# 04_LemonAutopilot_4.net
KiCad netlist of a schematic drawn in Altium Designer
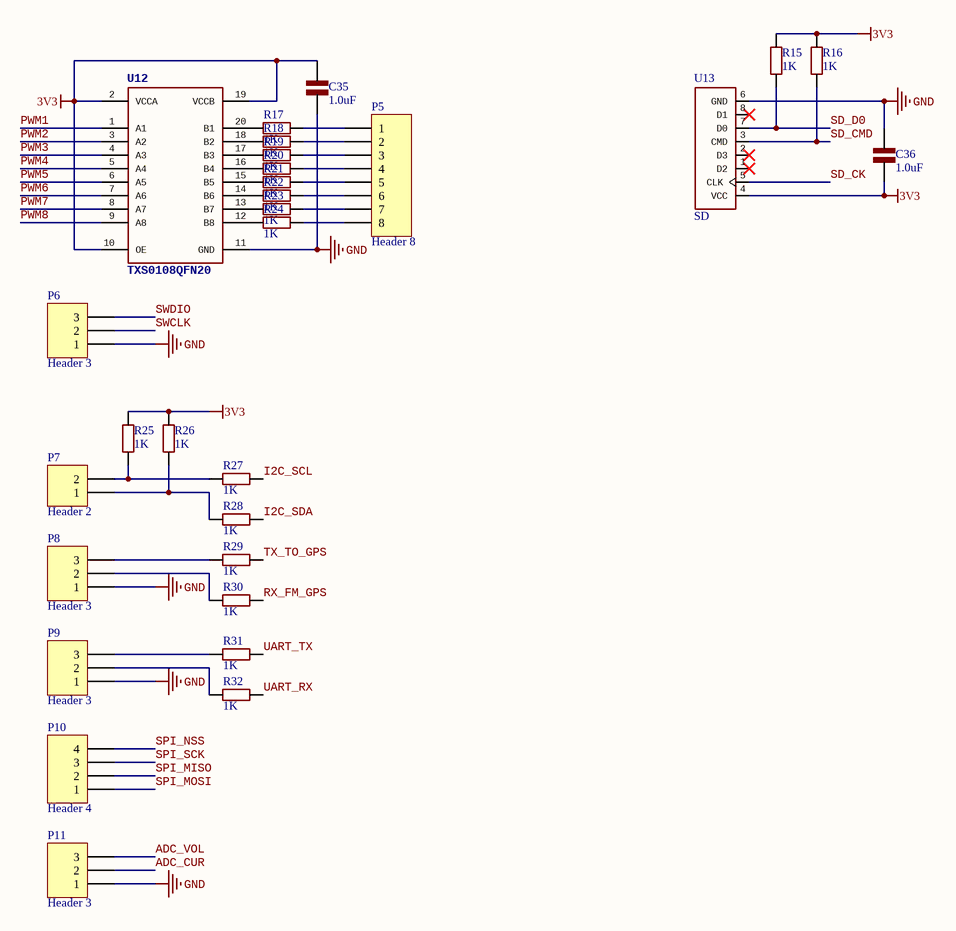
[diagram p0: 04.LemonAutopilot_4.SchDoc]

(export (version "E")
  (design (tool "Eeschema 10.0.6"))
  (components
    (comp (ref "C35") (value "1.0uF") (footprint "0603_C") (libsource (lib "Library") (part "C0603")))
    (comp (ref "C36") (value "1.0uF") (footprint "0603_C") (libsource (lib "Library") (part "C0603")))
    (comp (ref "P5")
      (value "Header 8")
      (footprint "HDR1X8")
      (description "Header, 8-Pin")
      (fields (field (name "PUBLISHER") "Altium Limited"))
      (libsource (lib "Miscellaneous Connectors") (part "Header 8"))
    )
    (comp (ref "P6")
      (value "Header 3")
      (footprint "HDR1X3")
      (description "Header, 3-Pin")
      (fields (field (name "PUBLISHER") "Altium Limited"))
      (libsource (lib "Miscellaneous Connectors") (part "Header 3"))
    )
    (comp (ref "P7")
      (value "Header 2")
      (footprint "HDR1X2")
      (description "Header, 2-Pin")
      (fields (field (name "PUBLISHER") "Altium Limited"))
      (libsource (lib "Miscellaneous Connectors") (part "Header 2"))
    )
    (comp (ref "P8")
      (value "Header 3")
      (footprint "HDR1X3")
      (description "Header, 3-Pin")
      (fields (field (name "PUBLISHER") "Altium Limited"))
      (libsource (lib "Miscellaneous Connectors") (part "Header 3"))
    )
    (comp (ref "P9")
      (value "Header 3")
      (footprint "HDR1X3")
      (description "Header, 3-Pin")
      (fields (field (name "PUBLISHER") "Altium Limited"))
      (libsource (lib "Miscellaneous Connectors") (part "Header 3"))
    )
    (comp (ref "P10")
      (value "Header 4")
      (footprint "HDR1X4")
      (description "Header, 4-Pin")
      (fields (field (name "PUBLISHER") "Altium Limited"))
      (libsource (lib "Miscellaneous Connectors") (part "Header 4"))
    )
    (comp (ref "P11")
      (value "Header 3")
      (footprint "HDR1X3")
      (description "Header, 3-Pin")
      (fields (field (name "PUBLISHER") "Altium Limited"))
      (libsource (lib "Miscellaneous Connectors") (part "Header 3"))
    )
    (comp (ref "R15") (value "1K") (footprint "0603_R") (libsource (lib "") (part "R0603_1")))
    (comp (ref "R16") (value "1K") (footprint "0603_R") (libsource (lib "") (part "R0603_1")))
    (comp (ref "R17") (value "1K") (footprint "0603_R") (libsource (lib "Library") (part "R0603")))
    (comp (ref "R18") (value "1K") (footprint "0603_R") (libsource (lib "Library") (part "R0603")))
    (comp (ref "R19") (value "1K") (footprint "0603_R") (libsource (lib "Library") (part "R0603")))
    (comp (ref "R20") (value "1K") (footprint "0603_R") (libsource (lib "Library") (part "R0603")))
    (comp (ref "R21") (value "1K") (footprint "0603_R") (libsource (lib "Library") (part "R0603")))
    (comp (ref "R22") (value "1K") (footprint "0603_R") (libsource (lib "Library") (part "R0603")))
    (comp (ref "R23") (value "1K") (footprint "0603_R") (libsource (lib "Library") (part "R0603")))
    (comp (ref "R24") (value "1K") (footprint "0603_R") (libsource (lib "Library") (part "R0603")))
    (comp (ref "R25") (value "1K") (footprint "0603_R") (libsource (lib "") (part "R0603_1")))
    (comp (ref "R26") (value "1K") (footprint "0603_R") (libsource (lib "") (part "R0603_1")))
    (comp (ref "R27") (value "1K") (footprint "0603_R") (libsource (lib "Library") (part "R0603")))
    (comp (ref "R28") (value "1K") (footprint "0603_R") (libsource (lib "Library") (part "R0603")))
    (comp (ref "R29") (value "1K") (footprint "0603_R") (libsource (lib "Library") (part "R0603")))
    (comp (ref "R30") (value "1K") (footprint "0603_R") (libsource (lib "Library") (part "R0603")))
    (comp (ref "R31") (value "1K") (footprint "0603_R") (libsource (lib "Library") (part "R0603")))
    (comp (ref "R32") (value "1K") (footprint "0603_R") (libsource (lib "Library") (part "R0603")))
    (comp (ref "U12")
      (value "TXS0108QFN20")
      (footprint "QFN20-RGY")
      (libsource (lib "Library") (part "TXS0108QFN20"))
    )
    (comp (ref "U13") (value "SD") (libsource (lib "Library") (part "SD")))
  )
  (nets
    (net (code "1") (name "/ADC_CUR") (class "Default")
      (node (ref "P11") (pin "2") (pinfunction "2_2") (pintype "passive"))
    )
    (net (code "2") (name "/ADC_VOL") (class "Default")
      (node (ref "P11") (pin "3") (pinfunction "3_3") (pintype "passive"))
    )
    (net (code "3") (name "/I2C_SCL") (class "Default")
      (node (ref "R27") (pin "2") (pinfunction "2_2") (pintype "passive"))
    )
    (net (code "4") (name "/I2C_SDA") (class "Default")
      (node (ref "R28") (pin "2") (pinfunction "2_2") (pintype "passive"))
    )
    (net (code "5") (name "/PWM1") (class "Default")
      (node (ref "U12") (pin "1") (pinfunction "A1_1") (pintype "passive"))
    )
    (net (code "6") (name "/PWM2") (class "Default")
      (node (ref "U12") (pin "3") (pinfunction "A2_3") (pintype "passive"))
    )
    (net (code "7") (name "/PWM3") (class "Default")
      (node (ref "U12") (pin "4") (pinfunction "A3_4") (pintype "passive"))
    )
    (net (code "8") (name "/PWM4") (class "Default")
      (node (ref "U12") (pin "5") (pinfunction "A4_5") (pintype "passive"))
    )
    (net (code "9") (name "/PWM5") (class "Default")
      (node (ref "U12") (pin "6") (pinfunction "A5_6") (pintype "passive"))
    )
    (net (code "10") (name "/PWM6") (class "Default")
      (node (ref "U12") (pin "7") (pinfunction "A6_7") (pintype "passive"))
    )
    (net (code "11") (name "/PWM7") (class "Default")
      (node (ref "U12") (pin "8") (pinfunction "A7_8") (pintype "passive"))
    )
    (net (code "12") (name "/PWM8") (class "Default")
      (node (ref "U12") (pin "9") (pinfunction "A8_9") (pintype "passive"))
    )
    (net (code "13") (name "/RX_FM_GPS") (class "Default")
      (node (ref "R30") (pin "2") (pinfunction "2_2") (pintype "passive"))
    )
    (net (code "14") (name "/SD_CK") (class "Default")
      (node (ref "U13") (pin "5") (pinfunction "CLK_5") (pintype "passive"))
    )
    (net (code "15") (name "/SD_CMD") (class "Default")
      (node (ref "R16") (pin "2") (pinfunction "2_2") (pintype "passive"))
      (node (ref "U13") (pin "3") (pinfunction "CMD_3") (pintype "passive"))
    )
    (net (code "16") (name "/SD_D0") (class "Default")
      (node (ref "R15") (pin "2") (pinfunction "2_2") (pintype "passive"))
      (node (ref "U13") (pin "7") (pinfunction "D0_7") (pintype "passive"))
    )
    (net (code "17") (name "/SPI_MISO") (class "Default")
      (node (ref "P10") (pin "2") (pinfunction "2_2") (pintype "passive"))
    )
    (net (code "18") (name "/SPI_MOSI") (class "Default")
      (node (ref "P10") (pin "1") (pinfunction "1_1") (pintype "passive"))
    )
    (net (code "19") (name "/SPI_NSS") (class "Default")
      (node (ref "P10") (pin "4") (pinfunction "4_4") (pintype "passive"))
    )
    (net (code "20") (name "/SPI_SCK") (class "Default")
      (node (ref "P10") (pin "3") (pinfunction "3_3") (pintype "passive"))
    )
    (net (code "21") (name "/SWCLK") (class "Default")
      (node (ref "P6") (pin "2") (pinfunction "2_2") (pintype "passive"))
    )
    (net (code "22") (name "/SWDIO") (class "Default")
      (node (ref "P6") (pin "3") (pinfunction "3_3") (pintype "passive"))
    )
    (net (code "23") (name "/TX_TO_GPS") (class "Default")
      (node (ref "R29") (pin "2") (pinfunction "2_2") (pintype "passive"))
    )
    (net (code "24") (name "/UART_RX") (class "Default")
      (node (ref "R32") (pin "2") (pinfunction "2_2") (pintype "passive"))
    )
    (net (code "25") (name "/UART_TX") (class "Default")
      (node (ref "R31") (pin "2") (pinfunction "2_2") (pintype "passive"))
    )
    (net (code "26") (name "3V3") (class "Default")
      (node (ref "C35") (pin "2") (pinfunction "2_2") (pintype "passive"))
      (node (ref "C36") (pin "1") (pinfunction "1_1") (pintype "passive"))
      (node (ref "R15") (pin "1") (pinfunction "1_1") (pintype "passive"))
      (node (ref "R16") (pin "1") (pinfunction "1_1") (pintype "passive"))
      (node (ref "R25") (pin "1") (pinfunction "1_1") (pintype "passive"))
      (node (ref "R26") (pin "1") (pinfunction "1_1") (pintype "passive"))
      (node (ref "U12") (pin "10") (pinfunction "OE_10") (pintype "passive"))
      (node (ref "U12") (pin "19") (pinfunction "VCCB_19") (pintype "passive"))
      (node (ref "U12") (pin "2") (pinfunction "VCCA_2") (pintype "passive"))
      (node (ref "U13") (pin "4") (pinfunction "VCC_4") (pintype "passive"))
    )
    (net (code "27") (name "GND") (class "Default")
      (node (ref "C35") (pin "1") (pinfunction "1_1") (pintype "passive"))
      (node (ref "C36") (pin "2") (pinfunction "2_2") (pintype "passive"))
      (node (ref "P11") (pin "1") (pinfunction "1_1") (pintype "passive"))
      (node (ref "P6") (pin "1") (pinfunction "1_1") (pintype "passive"))
      (node (ref "P8") (pin "1") (pinfunction "1_1") (pintype "passive"))
      (node (ref "P9") (pin "1") (pinfunction "1_1") (pintype "passive"))
      (node (ref "U12") (pin "11") (pinfunction "GND_11") (pintype "power_in"))
      (node (ref "U13") (pin "6") (pinfunction "GND_6") (pintype "power_in"))
    )
    (net (code "28") (name "Net-(P5-Pad1)") (class "Default")
      (node (ref "P5") (pin "1") (pinfunction "1_1") (pintype "passive"))
      (node (ref "R17") (pin "2") (pinfunction "2_2") (pintype "passive"))
    )
    (net (code "29") (name "Net-(P5-Pad2)") (class "Default")
      (node (ref "P5") (pin "2") (pinfunction "2_2") (pintype "passive"))
      (node (ref "R18") (pin "2") (pinfunction "2_2") (pintype "passive"))
    )
    (net (code "30") (name "Net-(P5-Pad3)") (class "Default")
      (node (ref "P5") (pin "3") (pinfunction "3_3") (pintype "passive"))
      (node (ref "R19") (pin "2") (pinfunction "2_2") (pintype "passive"))
    )
    (net (code "31") (name "Net-(P5-Pad4)") (class "Default")
      (node (ref "P5") (pin "4") (pinfunction "4_4") (pintype "passive"))
      (node (ref "R20") (pin "2") (pinfunction "2_2") (pintype "passive"))
    )
    (net (code "32") (name "Net-(P5-Pad5)") (class "Default")
      (node (ref "P5") (pin "5") (pinfunction "5_5") (pintype "passive"))
      (node (ref "R21") (pin "2") (pinfunction "2_2") (pintype "passive"))
    )
    (net (code "33") (name "Net-(P5-Pad6)") (class "Default")
      (node (ref "P5") (pin "6") (pinfunction "6_6") (pintype "passive"))
      (node (ref "R22") (pin "2") (pinfunction "2_2") (pintype "passive"))
    )
    (net (code "34") (name "Net-(P5-Pad7)") (class "Default")
      (node (ref "P5") (pin "7") (pinfunction "7_7") (pintype "passive"))
      (node (ref "R23") (pin "2") (pinfunction "2_2") (pintype "passive"))
    )
    (net (code "35") (name "Net-(P5-Pad8)") (class "Default")
      (node (ref "P5") (pin "8") (pinfunction "8_8") (pintype "passive"))
      (node (ref "R24") (pin "2") (pinfunction "2_2") (pintype "passive"))
    )
    (net (code "36") (name "Net-(P7-Pad1)") (class "Default")
      (node (ref "P7") (pin "1") (pinfunction "1_1") (pintype "passive"))
      (node (ref "R26") (pin "2") (pinfunction "2_2") (pintype "passive"))
      (node (ref "R28") (pin "1") (pinfunction "1_1") (pintype "passive"))
    )
    (net (code "37") (name "Net-(P7-Pad2)") (class "Default")
      (node (ref "P7") (pin "2") (pinfunction "2_2") (pintype "passive"))
      (node (ref "R25") (pin "2") (pinfunction "2_2") (pintype "passive"))
      (node (ref "R27") (pin "1") (pinfunction "1_1") (pintype "passive"))
    )
    (net (code "38") (name "Net-(P8-Pad2)") (class "Default")
      (node (ref "P8") (pin "2") (pinfunction "2_2") (pintype "passive"))
      (node (ref "R30") (pin "1") (pinfunction "1_1") (pintype "passive"))
    )
    (net (code "39") (name "Net-(P8-Pad3)") (class "Default")
      (node (ref "P8") (pin "3") (pinfunction "3_3") (pintype "passive"))
      (node (ref "R29") (pin "1") (pinfunction "1_1") (pintype "passive"))
    )
    (net (code "40") (name "Net-(P9-Pad2)") (class "Default")
      (node (ref "P9") (pin "2") (pinfunction "2_2") (pintype "passive"))
      (node (ref "R32") (pin "1") (pinfunction "1_1") (pintype "passive"))
    )
    (net (code "41") (name "Net-(P9-Pad3)") (class "Default")
      (node (ref "P9") (pin "3") (pinfunction "3_3") (pintype "passive"))
      (node (ref "R31") (pin "1") (pinfunction "1_1") (pintype "passive"))
    )
    (net (code "42") (name "Net-(U12-B1)") (class "Default")
      (node (ref "R17") (pin "1") (pinfunction "1_1") (pintype "passive"))
      (node (ref "U12") (pin "20") (pinfunction "B1_20") (pintype "passive"))
    )
    (net (code "43") (name "Net-(U12-B2)") (class "Default")
      (node (ref "R18") (pin "1") (pinfunction "1_1") (pintype "passive"))
      (node (ref "U12") (pin "18") (pinfunction "B2_18") (pintype "passive"))
    )
    (net (code "44") (name "Net-(U12-B3)") (class "Default")
      (node (ref "R19") (pin "1") (pinfunction "1_1") (pintype "passive"))
      (node (ref "U12") (pin "17") (pinfunction "B3_17") (pintype "passive"))
    )
    (net (code "45") (name "Net-(U12-B4)") (class "Default")
      (node (ref "R20") (pin "1") (pinfunction "1_1") (pintype "passive"))
      (node (ref "U12") (pin "16") (pinfunction "B4_16") (pintype "passive"))
    )
    (net (code "46") (name "Net-(U12-B5)") (class "Default")
      (node (ref "R21") (pin "1") (pinfunction "1_1") (pintype "passive"))
      (node (ref "U12") (pin "15") (pinfunction "B5_15") (pintype "passive"))
    )
    (net (code "47") (name "Net-(U12-B6)") (class "Default")
      (node (ref "R22") (pin "1") (pinfunction "1_1") (pintype "passive"))
      (node (ref "U12") (pin "14") (pinfunction "B6_14") (pintype "passive"))
    )
    (net (code "48") (name "Net-(U12-B7)") (class "Default")
      (node (ref "R23") (pin "1") (pinfunction "1_1") (pintype "passive"))
      (node (ref "U12") (pin "13") (pinfunction "B7_13") (pintype "passive"))
    )
    (net (code "49") (name "Net-(U12-B8)") (class "Default")
      (node (ref "R24") (pin "1") (pinfunction "1_1") (pintype "passive"))
      (node (ref "U12") (pin "12") (pinfunction "B8_12") (pintype "passive"))
    )
    (net (code "50") (name "unconnected-(U13-D1-Pad8)") (class "Default")
      (node (ref "U13") (pin "8") (pinfunction "D1_8") (pintype "passive+no_connect"))
    )
    (net (code "51") (name "unconnected-(U13-D2-Pad1)") (class "Default")
      (node (ref "U13") (pin "1") (pinfunction "D2_1") (pintype "passive+no_connect"))
    )
    (net (code "52") (name "unconnected-(U13-D3-Pad2)") (class "Default")
      (node (ref "U13") (pin "2") (pinfunction "D3_2") (pintype "passive+no_connect"))
    )
  )
)
